# Schematic_rfclock_frontend.net
KiCad netlist of a schematic drawn in EAGLE
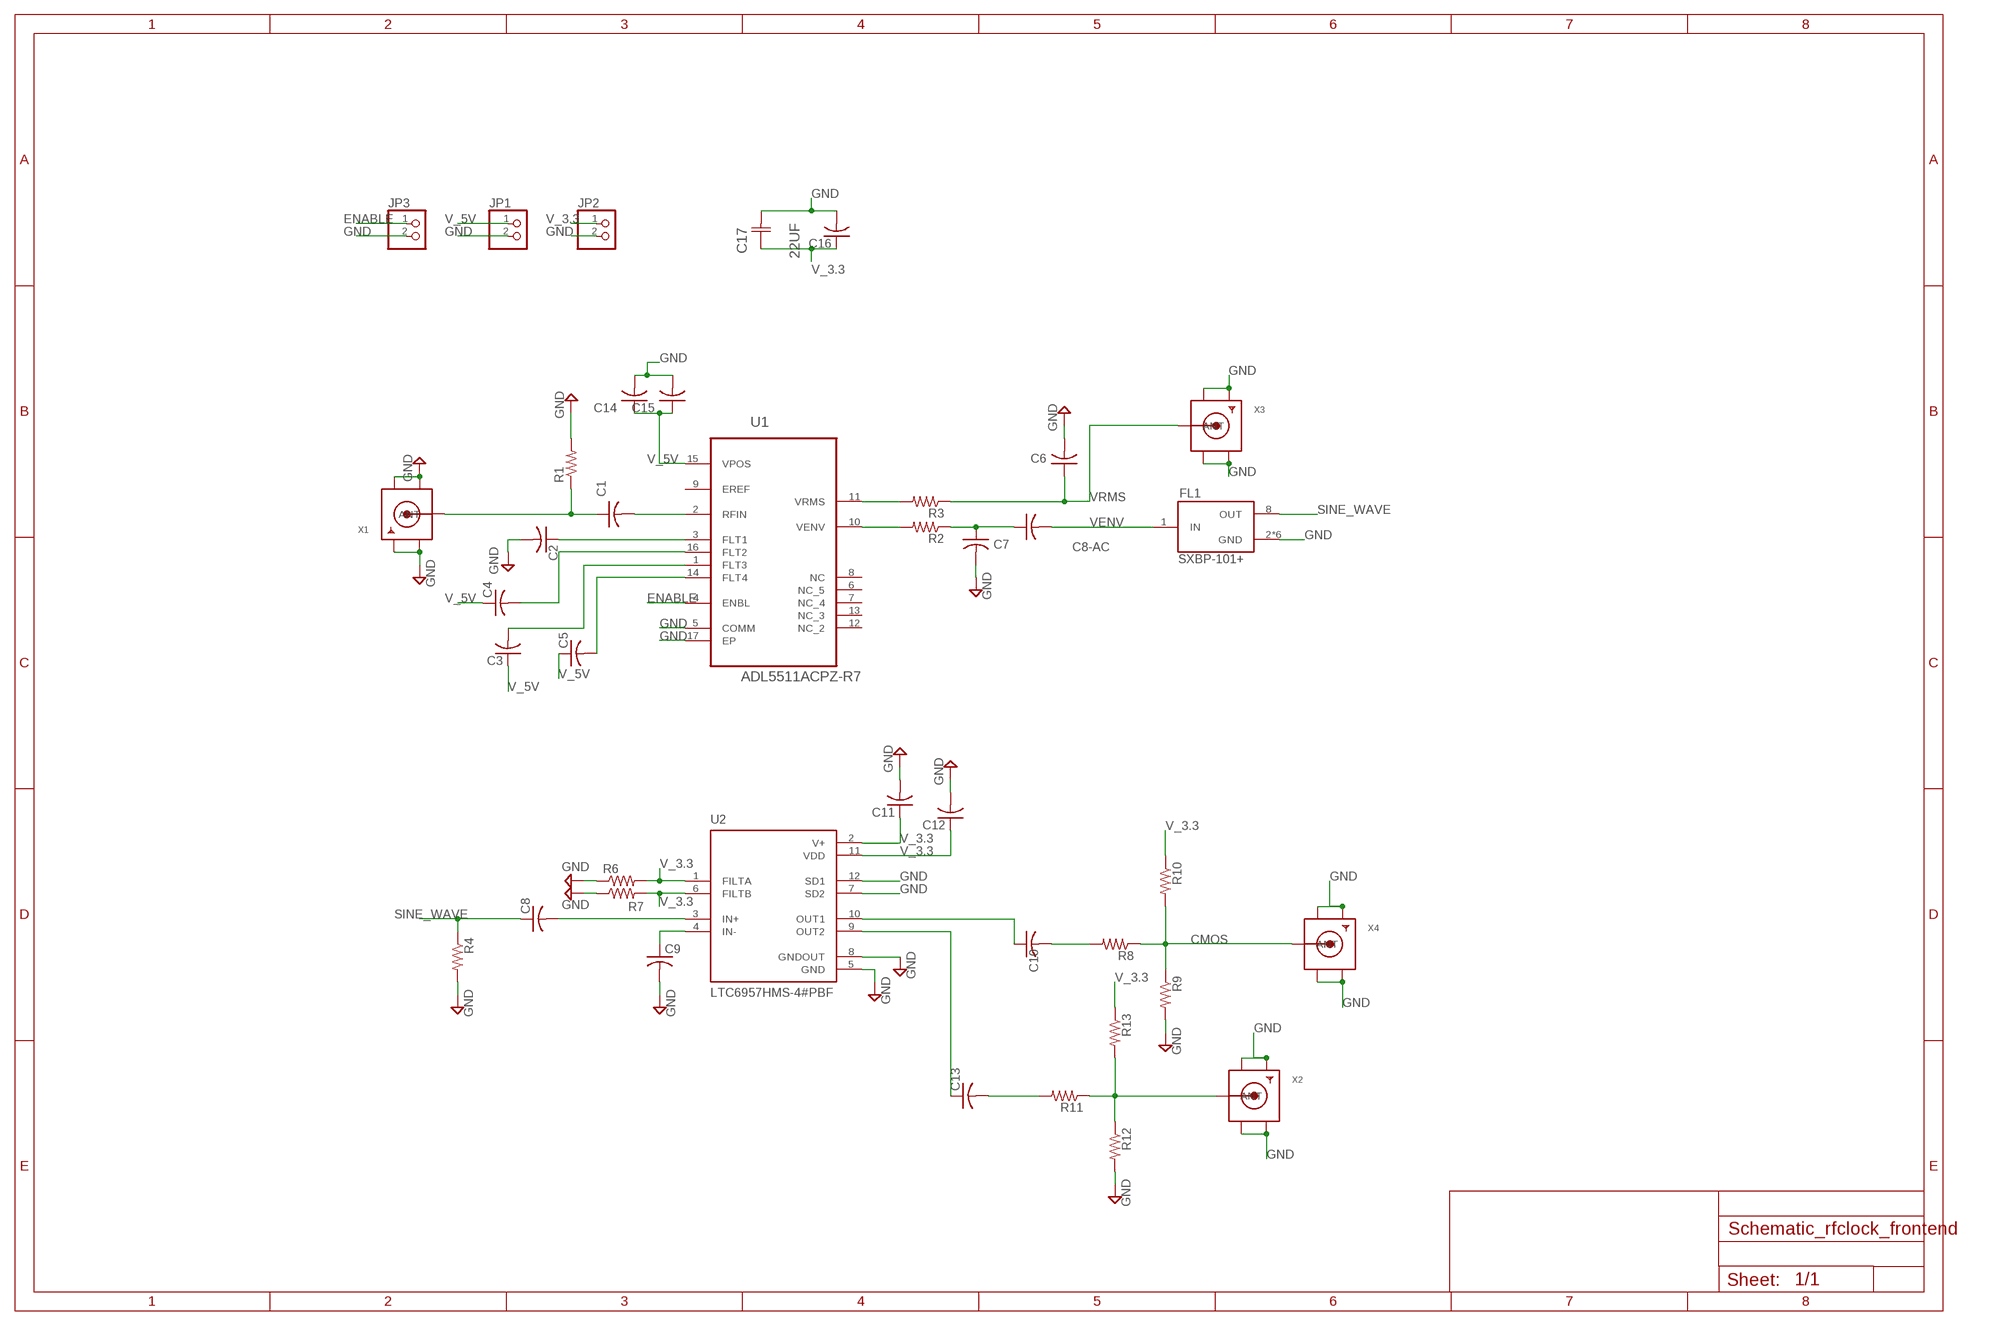
[diagram p0: schematic, sheet 1]

(export (version "E")
  (design (tool "Eeschema 10.0.6"))
  (components
    (comp (ref "C1")
      (value "C-USC0402K")
      (footprint "eagle-import:C0402K")
      (libsource (lib "eagle-import") (part "C-USC0402K"))
    )
    (comp (ref "C2")
      (value "C-USC0402K")
      (footprint "eagle-import:C0402K")
      (libsource (lib "eagle-import") (part "C-USC0402K"))
    )
    (comp (ref "C3")
      (value "C-USC0402")
      (footprint "eagle-import:C0402")
      (libsource (lib "eagle-import") (part "C-USC0402"))
    )
    (comp (ref "C4")
      (value "C-USC0402")
      (footprint "eagle-import:C0402")
      (libsource (lib "eagle-import") (part "C-USC0402"))
    )
    (comp (ref "C5")
      (value "C-USC0402")
      (footprint "eagle-import:C0402")
      (libsource (lib "eagle-import") (part "C-USC0402"))
    )
    (comp (ref "C6")
      (value "C-USC0402")
      (footprint "eagle-import:C0402")
      (libsource (lib "eagle-import") (part "C-USC0402"))
    )
    (comp (ref "C7")
      (value "C-USC0402")
      (footprint "eagle-import:C0402")
      (libsource (lib "eagle-import") (part "C-USC0402"))
    )
    (comp (ref "C8")
      (value "C-USC0603")
      (footprint "eagle-import:C0603")
      (libsource (lib "eagle-import") (part "C-USC0603"))
    )
    (comp (ref "C8-AC")
      (value "C-USC0402K")
      (footprint "eagle-import:C0402K")
      (libsource (lib "eagle-import") (part "C-USC0402K"))
    )
    (comp (ref "C9")
      (value "C-USC0603")
      (footprint "eagle-import:C0603")
      (libsource (lib "eagle-import") (part "C-USC0603"))
    )
    (comp (ref "C10")
      (value "C-USC0603K")
      (footprint "eagle-import:C0603K")
      (libsource (lib "eagle-import") (part "C-USC0603K"))
    )
    (comp (ref "C11")
      (value "C-USC0603K")
      (footprint "eagle-import:C0603K")
      (libsource (lib "eagle-import") (part "C-USC0603K"))
    )
    (comp (ref "C12")
      (value "C-USC0603K")
      (footprint "eagle-import:C0603K")
      (libsource (lib "eagle-import") (part "C-USC0603K"))
    )
    (comp (ref "C13")
      (value "C-USC0603K")
      (footprint "eagle-import:C0603K")
      (libsource (lib "eagle-import") (part "C-USC0603K"))
    )
    (comp (ref "C14")
      (value "C-USC0402")
      (footprint "eagle-import:C0402")
      (libsource (lib "eagle-import") (part "C-USC0402"))
    )
    (comp (ref "C15")
      (value "C-USC0402")
      (footprint "eagle-import:C0402")
      (libsource (lib "eagle-import") (part "C-USC0402"))
    )
    (comp (ref "C16")
      (value "C-USC0603")
      (footprint "eagle-import:C0603")
      (libsource (lib "eagle-import") (part "C-USC0603"))
    )
    (comp (ref "C17")
      (value "22UF")
      (footprint "eagle-import:CAPCP3528X210N")
      (fields (field (name "MPN") "TPSB226M010R0700"))
      (libsource (lib "eagle-import") (part "TPSB226M010R0700"))
    )
    (comp (ref "FL1")
      (value "SXBP-101+")
      (footprint "eagle-import:FIL_SXBP-101+")
      (fields (field (name "MF") "Mini-Circuits"))
      (libsource (lib "eagle-import") (part "SXBP-101+"))
    )
    (comp (ref "JP1")
      (value "PINHD-1X2")
      (footprint "eagle-import:1X02")
      (libsource (lib "eagle-import") (part "PINHD-1X2"))
    )
    (comp (ref "JP2")
      (value "PINHD-1X2")
      (footprint "eagle-import:1X02")
      (libsource (lib "eagle-import") (part "PINHD-1X2"))
    )
    (comp (ref "JP3")
      (value "PINHD-1X2")
      (footprint "eagle-import:1X02")
      (libsource (lib "eagle-import") (part "PINHD-1X2"))
    )
    (comp (ref "R1")
      (value "R-US_R0402")
      (footprint "eagle-import:R0402")
      (libsource (lib "eagle-import") (part "R-US_R0402"))
    )
    (comp (ref "R2")
      (value "R-US_R0402")
      (footprint "eagle-import:R0402")
      (libsource (lib "eagle-import") (part "R-US_R0402"))
    )
    (comp (ref "R3")
      (value "R-US_R0402")
      (footprint "eagle-import:R0402")
      (libsource (lib "eagle-import") (part "R-US_R0402"))
    )
    (comp (ref "R4")
      (value "R-US_R0603")
      (footprint "eagle-import:R0603")
      (libsource (lib "eagle-import") (part "R-US_R0603"))
    )
    (comp (ref "R6")
      (value "R-US_R0603")
      (footprint "eagle-import:R0603")
      (libsource (lib "eagle-import") (part "R-US_R0603"))
    )
    (comp (ref "R7")
      (value "R-US_R0603")
      (footprint "eagle-import:R0603")
      (libsource (lib "eagle-import") (part "R-US_R0603"))
    )
    (comp (ref "R8")
      (value "R-US_R0603")
      (footprint "eagle-import:R0603")
      (libsource (lib "eagle-import") (part "R-US_R0603"))
    )
    (comp (ref "R9")
      (value "R-US_R0603")
      (footprint "eagle-import:R0603")
      (libsource (lib "eagle-import") (part "R-US_R0603"))
    )
    (comp (ref "R10")
      (value "R-US_R0603")
      (footprint "eagle-import:R0603")
      (libsource (lib "eagle-import") (part "R-US_R0603"))
    )
    (comp (ref "R11")
      (value "R-US_R0603")
      (footprint "eagle-import:R0603")
      (libsource (lib "eagle-import") (part "R-US_R0603"))
    )
    (comp (ref "R12")
      (value "R-US_R0603")
      (footprint "eagle-import:R0603")
      (libsource (lib "eagle-import") (part "R-US_R0603"))
    )
    (comp (ref "R13")
      (value "R-US_R0603")
      (footprint "eagle-import:R0603")
      (libsource (lib "eagle-import") (part "R-US_R0603"))
    )
    (comp (ref "U1")
      (value "ADL5511ACPZ-R7")
      (footprint "eagle-import:QFN50P300X300X80-17N")
      (fields (field (name "MF") "Analog Devices"))
      (libsource (lib "eagle-import") (part "ADL5511ACPZ-R7"))
    )
    (comp (ref "U2")
      (value "LTC6957HMS-4#PBF")
      (footprint "eagle-import:SOP65P490X110-12N")
      (fields (field (name "MF") "Analog Devices"))
      (libsource (lib "eagle-import") (part "LTC6957HMS-4#PBF"))
    )
    (comp (ref "X1")
      (value "SMACONNECTOR_EDGE")
      (footprint "eagle-import:SMA_EDGELAUNCH")
      (libsource (lib "eagle-import") (part "SMACONNECTOR_EDGE"))
    )
    (comp (ref "X2")
      (value "SMACONNECTOR_EDGE")
      (footprint "eagle-import:SMA_EDGELAUNCH")
      (libsource (lib "eagle-import") (part "SMACONNECTOR_EDGE"))
    )
    (comp (ref "X3")
      (value "SMACONNECTOR_EDGE")
      (footprint "eagle-import:SMA_EDGELAUNCH")
      (libsource (lib "eagle-import") (part "SMACONNECTOR_EDGE"))
    )
    (comp (ref "X4")
      (value "SMACONNECTOR_EDGE")
      (footprint "eagle-import:SMA_EDGELAUNCH")
      (libsource (lib "eagle-import") (part "SMACONNECTOR_EDGE"))
    )
  )
  (nets
    (net (code "1") (name "/CMOS") (class "Default")
      (node (ref "R10") (pin "2") (pinfunction "2_2") (pintype "passive"))
      (node (ref "R8") (pin "1") (pinfunction "1_1") (pintype "passive"))
      (node (ref "R9") (pin "1") (pinfunction "1_1") (pintype "passive"))
      (node (ref "X4") (pin "P") (pinfunction "ANT_P") (pintype "bidirectional"))
    )
    (net (code "2") (name "/ENABLE") (class "Default")
      (node (ref "JP3") (pin "1") (pinfunction "1_1") (pintype "passive"))
      (node (ref "U1") (pin "4") (pinfunction "ENBL_4") (pintype "passive"))
    )
    (net (code "3") (name "/SINE_WAVE") (class "Default")
      (node (ref "C8") (pin "1") (pinfunction "1_1") (pintype "passive"))
      (node (ref "FL1") (pin "8") (pinfunction "OUT_8") (pintype "output"))
      (node (ref "R4") (pin "1") (pinfunction "1_1") (pintype "passive"))
    )
    (net (code "4") (name "/VENV") (class "Default")
      (node (ref "C8-AC") (pin "2") (pinfunction "2_2") (pintype "passive"))
      (node (ref "FL1") (pin "1") (pinfunction "IN_1") (pintype "input"))
    )
    (net (code "5") (name "/VRMS") (class "Default")
      (node (ref "C6") (pin "1") (pinfunction "1_1") (pintype "passive"))
      (node (ref "R3") (pin "1") (pinfunction "1_1") (pintype "passive"))
      (node (ref "X3") (pin "P") (pinfunction "ANT_P") (pintype "bidirectional"))
    )
    (net (code "6") (name "/V_3.3") (class "Default")
      (node (ref "C11") (pin "1") (pinfunction "1_1") (pintype "passive"))
      (node (ref "C12") (pin "1") (pinfunction "1_1") (pintype "passive"))
      (node (ref "C16") (pin "1") (pinfunction "1_1") (pintype "passive"))
      (node (ref "C17") (pin "1") (pinfunction "C1_1") (pintype "passive"))
      (node (ref "JP2") (pin "1") (pinfunction "1_1") (pintype "passive"))
      (node (ref "R10") (pin "1") (pinfunction "1_1") (pintype "passive"))
      (node (ref "R13") (pin "1") (pinfunction "1_1") (pintype "passive"))
      (node (ref "R6") (pin "2") (pinfunction "2_2") (pintype "passive"))
      (node (ref "R7") (pin "2") (pinfunction "2_2") (pintype "passive"))
      (node (ref "U2") (pin "1") (pinfunction "FILTA_1") (pintype "input"))
      (node (ref "U2") (pin "11") (pinfunction "VDD_11") (pintype "power_in"))
      (node (ref "U2") (pin "2") (pinfunction "V+_2") (pintype "power_in"))
      (node (ref "U2") (pin "6") (pinfunction "FILTB_6") (pintype "input"))
    )
    (net (code "7") (name "/V_5V") (class "Default")
      (node (ref "C14") (pin "1") (pinfunction "1_1") (pintype "passive"))
      (node (ref "C15") (pin "1") (pinfunction "1_1") (pintype "passive"))
      (node (ref "C3") (pin "1") (pinfunction "1_1") (pintype "passive"))
      (node (ref "C4") (pin "1") (pinfunction "1_1") (pintype "passive"))
      (node (ref "C5") (pin "1") (pinfunction "1_1") (pintype "passive"))
      (node (ref "JP1") (pin "1") (pinfunction "1_1") (pintype "passive"))
      (node (ref "U1") (pin "15") (pinfunction "VPOS_15") (pintype "passive"))
    )
    (net (code "8") (name "GND") (class "Default")
      (node (ref "C11") (pin "2") (pinfunction "2_2") (pintype "passive"))
      (node (ref "C12") (pin "2") (pinfunction "2_2") (pintype "passive"))
      (node (ref "C14") (pin "2") (pinfunction "2_2") (pintype "passive"))
      (node (ref "C15") (pin "2") (pinfunction "2_2") (pintype "passive"))
      (node (ref "C16") (pin "2") (pinfunction "2_2") (pintype "passive"))
      (node (ref "C17") (pin "2") (pinfunction "C2_2") (pintype "passive"))
      (node (ref "C2") (pin "2") (pinfunction "2_2") (pintype "passive"))
      (node (ref "C6") (pin "2") (pinfunction "2_2") (pintype "passive"))
      (node (ref "C7") (pin "2") (pinfunction "2_2") (pintype "passive"))
      (node (ref "C9") (pin "2") (pinfunction "2_2") (pintype "passive"))
      (node (ref "FL1") (pin "2") (pinfunction "GND_2") (pintype "power_in"))
      (node (ref "FL1") (pin "3") (pinfunction "GND_3") (pintype "power_in"))
      (node (ref "FL1") (pin "4") (pinfunction "GND_4") (pintype "power_in"))
      (node (ref "FL1") (pin "5") (pinfunction "GND_5") (pintype "power_in"))
      (node (ref "FL1") (pin "6") (pinfunction "GND_6") (pintype "power_in"))
      (node (ref "FL1") (pin "7") (pinfunction "GND_7") (pintype "power_in"))
      (node (ref "JP1") (pin "2") (pinfunction "2_2") (pintype "passive"))
      (node (ref "JP2") (pin "2") (pinfunction "2_2") (pintype "passive"))
      (node (ref "JP3") (pin "2") (pinfunction "2_2") (pintype "passive"))
      (node (ref "R1") (pin "2") (pinfunction "2_2") (pintype "passive"))
      (node (ref "R12") (pin "2") (pinfunction "2_2") (pintype "passive"))
      (node (ref "R4") (pin "2") (pinfunction "2_2") (pintype "passive"))
      (node (ref "R6") (pin "1") (pinfunction "1_1") (pintype "passive"))
      (node (ref "R7") (pin "1") (pinfunction "1_1") (pintype "passive"))
      (node (ref "R9") (pin "2") (pinfunction "2_2") (pintype "passive"))
      (node (ref "U1") (pin "17") (pinfunction "EP_17") (pintype "passive"))
      (node (ref "U1") (pin "5") (pinfunction "COMM_5") (pintype "passive"))
      (node (ref "U2") (pin "12") (pinfunction "SD1_12") (pintype "output"))
      (node (ref "U2") (pin "5") (pinfunction "GND_5") (pintype "power_in"))
      (node (ref "U2") (pin "7") (pinfunction "SD2_7") (pintype "output"))
      (node (ref "U2") (pin "8") (pinfunction "GNDOUT_8") (pintype "power_in"))
      (node (ref "X1") (pin "GND@1") (pinfunction "GND4_GND@1") (pintype "power_in"))
      (node (ref "X1") (pin "GND@2") (pinfunction "GND3_GND@2") (pintype "power_in"))
      (node (ref "X1") (pin "GND@3") (pinfunction "GND2_GND@3") (pintype "power_in"))
      (node (ref "X1") (pin "GND@4") (pinfunction "GND1_GND@4") (pintype "power_in"))
      (node (ref "X2") (pin "GND@1") (pinfunction "GND4_GND@1") (pintype "power_in"))
      (node (ref "X2") (pin "GND@2") (pinfunction "GND3_GND@2") (pintype "power_in"))
      (node (ref "X2") (pin "GND@3") (pinfunction "GND2_GND@3") (pintype "power_in"))
      (node (ref "X2") (pin "GND@4") (pinfunction "GND1_GND@4") (pintype "power_in"))
      (node (ref "X3") (pin "GND@1") (pinfunction "GND4_GND@1") (pintype "power_in"))
      (node (ref "X3") (pin "GND@2") (pinfunction "GND3_GND@2") (pintype "power_in"))
      (node (ref "X3") (pin "GND@3") (pinfunction "GND2_GND@3") (pintype "power_in"))
      (node (ref "X3") (pin "GND@4") (pinfunction "GND1_GND@4") (pintype "power_in"))
      (node (ref "X4") (pin "GND@1") (pinfunction "GND4_GND@1") (pintype "power_in"))
      (node (ref "X4") (pin "GND@2") (pinfunction "GND3_GND@2") (pintype "power_in"))
      (node (ref "X4") (pin "GND@3") (pinfunction "GND2_GND@3") (pintype "power_in"))
      (node (ref "X4") (pin "GND@4") (pinfunction "GND1_GND@4") (pintype "power_in"))
    )
    (net (code "9") (name "Net-(C7-Pad1)") (class "Default")
      (node (ref "C7") (pin "1") (pinfunction "1_1") (pintype "passive"))
      (node (ref "C8-AC") (pin "1") (pinfunction "1_1") (pintype "passive"))
      (node (ref "R2") (pin "1") (pinfunction "1_1") (pintype "passive"))
    )
    (net (code "10") (name "Net-(C10-Pad2)") (class "Default")
      (node (ref "C10") (pin "2") (pinfunction "2_2") (pintype "passive"))
      (node (ref "R8") (pin "2") (pinfunction "2_2") (pintype "passive"))
    )
    (net (code "11") (name "Net-(C13-Pad2)") (class "Default")
      (node (ref "C13") (pin "2") (pinfunction "2_2") (pintype "passive"))
      (node (ref "R11") (pin "2") (pinfunction "2_2") (pintype "passive"))
    )
    (net (code "12") (name "Net-(U1-FLT1)") (class "Default")
      (node (ref "C2") (pin "1") (pinfunction "1_1") (pintype "passive"))
      (node (ref "U1") (pin "3") (pinfunction "FLT1_3") (pintype "passive"))
    )
    (net (code "13") (name "Net-(U1-FLT2)") (class "Default")
      (node (ref "C4") (pin "2") (pinfunction "2_2") (pintype "passive"))
      (node (ref "U1") (pin "16") (pinfunction "FLT2_16") (pintype "passive"))
    )
    (net (code "14") (name "Net-(U1-FLT3)") (class "Default")
      (node (ref "C3") (pin "2") (pinfunction "2_2") (pintype "passive"))
      (node (ref "U1") (pin "1") (pinfunction "FLT3_1") (pintype "passive"))
    )
    (net (code "15") (name "Net-(U1-FLT4)") (class "Default")
      (node (ref "C5") (pin "2") (pinfunction "2_2") (pintype "passive"))
      (node (ref "U1") (pin "14") (pinfunction "FLT4_14") (pintype "passive"))
    )
    (net (code "16") (name "Net-(U1-RFIN)") (class "Default")
      (node (ref "C1") (pin "2") (pinfunction "2_2") (pintype "passive"))
      (node (ref "U1") (pin "2") (pinfunction "RFIN_2") (pintype "passive"))
    )
    (net (code "17") (name "Net-(U1-VENV)") (class "Default")
      (node (ref "R2") (pin "2") (pinfunction "2_2") (pintype "passive"))
      (node (ref "U1") (pin "10") (pinfunction "VENV_10") (pintype "passive"))
    )
    (net (code "18") (name "Net-(U1-VRMS)") (class "Default")
      (node (ref "R3") (pin "2") (pinfunction "2_2") (pintype "passive"))
      (node (ref "U1") (pin "11") (pinfunction "VRMS_11") (pintype "passive"))
    )
    (net (code "19") (name "Net-(U2-IN+)") (class "Default")
      (node (ref "C8") (pin "2") (pinfunction "2_2") (pintype "passive"))
      (node (ref "U2") (pin "3") (pinfunction "IN+_3") (pintype "input"))
    )
    (net (code "20") (name "Net-(U2-IN-)") (class "Default")
      (node (ref "C9") (pin "1") (pinfunction "1_1") (pintype "passive"))
      (node (ref "U2") (pin "4") (pinfunction "IN-_4") (pintype "input"))
    )
    (net (code "21") (name "Net-(U2-OUT1)") (class "Default")
      (node (ref "C10") (pin "1") (pinfunction "1_1") (pintype "passive"))
      (node (ref "U2") (pin "10") (pinfunction "OUT1_10") (pintype "output"))
    )
    (net (code "22") (name "Net-(U2-OUT2)") (class "Default")
      (node (ref "C13") (pin "1") (pinfunction "1_1") (pintype "passive"))
      (node (ref "U2") (pin "9") (pinfunction "OUT2_9") (pintype "output"))
    )
    (net (code "23") (name "Net-(X1-ANT)") (class "Default")
      (node (ref "C1") (pin "1") (pinfunction "1_1") (pintype "passive"))
      (node (ref "R1") (pin "1") (pinfunction "1_1") (pintype "passive"))
      (node (ref "X1") (pin "P") (pinfunction "ANT_P") (pintype "bidirectional"))
    )
    (net (code "24") (name "Net-(X2-ANT)") (class "Default")
      (node (ref "R11") (pin "1") (pinfunction "1_1") (pintype "passive"))
      (node (ref "R12") (pin "1") (pinfunction "1_1") (pintype "passive"))
      (node (ref "R13") (pin "2") (pinfunction "2_2") (pintype "passive"))
      (node (ref "X2") (pin "P") (pinfunction "ANT_P") (pintype "bidirectional"))
    )
    (net (code "25") (name "unconnected-(U1-EREF-Pad9)") (class "Default")
      (node (ref "U1") (pin "9") (pinfunction "EREF_9") (pintype "passive"))
    )
    (net (code "26") (name "unconnected-(U1-NC-Pad8)") (class "Default")
      (node (ref "U1") (pin "8") (pinfunction "NC_8") (pintype "passive"))
    )
    (net (code "27") (name "unconnected-(U1-NC_2-Pad12)") (class "Default")
      (node (ref "U1") (pin "12") (pinfunction "NC_2_12") (pintype "passive"))
    )
    (net (code "28") (name "unconnected-(U1-NC_3-Pad13)") (class "Default")
      (node (ref "U1") (pin "13") (pinfunction "NC_3_13") (pintype "passive"))
    )
    (net (code "29") (name "unconnected-(U1-NC_4-Pad7)") (class "Default")
      (node (ref "U1") (pin "7") (pinfunction "NC_4_7") (pintype "passive"))
    )
    (net (code "30") (name "unconnected-(U1-NC_5-Pad6)") (class "Default")
      (node (ref "U1") (pin "6") (pinfunction "NC_5_6") (pintype "passive"))
    )
  )
)
